# Rtx_Power_Filter.net
KiCad netlist of a schematic drawn in EAGLE
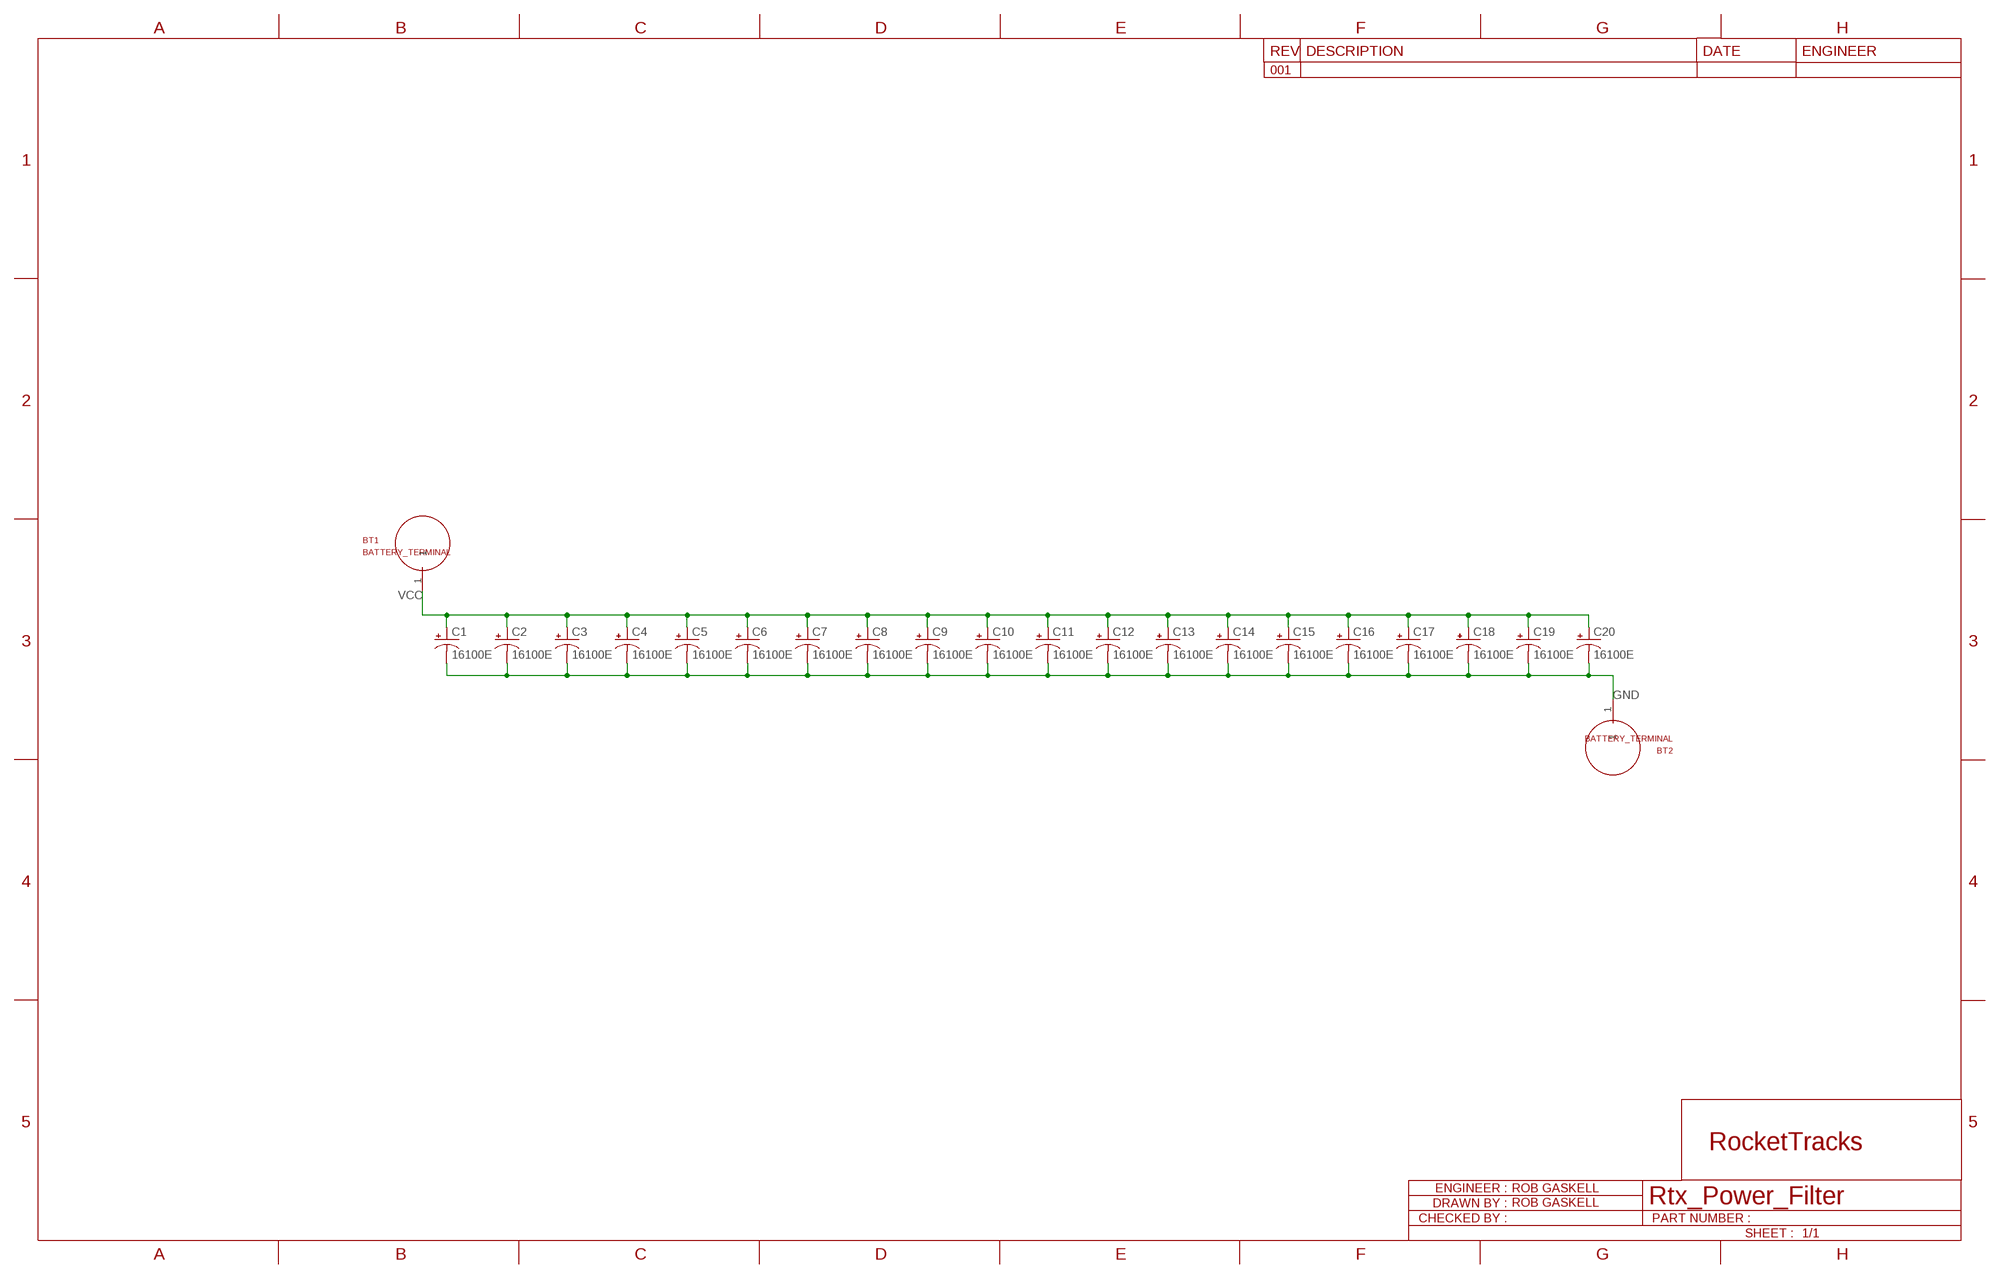
[diagram p0: schematic, sheet 1]

(export (version "E")
  (design (tool "Eeschema 10.0.6"))
  (components
    (comp (ref "BT1")
      (value "BATTERY_TERMINAL")
      (footprint "eagle-import:BATTERY_TERMINAL")
      (libsource (lib "eagle-import") (part "BATTERY_TERMINAL"))
    )
    (comp (ref "BT2")
      (value "BATTERY_TERMINAL")
      (footprint "eagle-import:BATTERY_TERMINAL")
      (libsource (lib "eagle-import") (part "BATTERY_TERMINAL"))
    )
    (comp (ref "C1")
      (value "16100E")
      (footprint "eagle-import:16100")
      (libsource (lib "eagle-import") (part "16100E"))
    )
    (comp (ref "C2")
      (value "16100E")
      (footprint "eagle-import:16100")
      (libsource (lib "eagle-import") (part "16100E"))
    )
    (comp (ref "C3")
      (value "16100E")
      (footprint "eagle-import:16100")
      (libsource (lib "eagle-import") (part "16100E"))
    )
    (comp (ref "C4")
      (value "16100E")
      (footprint "eagle-import:16100")
      (libsource (lib "eagle-import") (part "16100E"))
    )
    (comp (ref "C5")
      (value "16100E")
      (footprint "eagle-import:16100")
      (libsource (lib "eagle-import") (part "16100E"))
    )
    (comp (ref "C6")
      (value "16100E")
      (footprint "eagle-import:16100")
      (libsource (lib "eagle-import") (part "16100E"))
    )
    (comp (ref "C7")
      (value "16100E")
      (footprint "eagle-import:16100")
      (libsource (lib "eagle-import") (part "16100E"))
    )
    (comp (ref "C8")
      (value "16100E")
      (footprint "eagle-import:16100")
      (libsource (lib "eagle-import") (part "16100E"))
    )
    (comp (ref "C9")
      (value "16100E")
      (footprint "eagle-import:16100")
      (libsource (lib "eagle-import") (part "16100E"))
    )
    (comp (ref "C10")
      (value "16100E")
      (footprint "eagle-import:16100")
      (libsource (lib "eagle-import") (part "16100E"))
    )
    (comp (ref "C11")
      (value "16100E")
      (footprint "eagle-import:16100")
      (libsource (lib "eagle-import") (part "16100E"))
    )
    (comp (ref "C12")
      (value "16100E")
      (footprint "eagle-import:16100")
      (libsource (lib "eagle-import") (part "16100E"))
    )
    (comp (ref "C13")
      (value "16100E")
      (footprint "eagle-import:16100")
      (libsource (lib "eagle-import") (part "16100E"))
    )
    (comp (ref "C14")
      (value "16100E")
      (footprint "eagle-import:16100")
      (libsource (lib "eagle-import") (part "16100E"))
    )
    (comp (ref "C15")
      (value "16100E")
      (footprint "eagle-import:16100")
      (libsource (lib "eagle-import") (part "16100E"))
    )
    (comp (ref "C16")
      (value "16100E")
      (footprint "eagle-import:16100")
      (libsource (lib "eagle-import") (part "16100E"))
    )
    (comp (ref "C17")
      (value "16100E")
      (footprint "eagle-import:16100")
      (libsource (lib "eagle-import") (part "16100E"))
    )
    (comp (ref "C18")
      (value "16100E")
      (footprint "eagle-import:16100")
      (libsource (lib "eagle-import") (part "16100E"))
    )
    (comp (ref "C19")
      (value "16100E")
      (footprint "eagle-import:16100")
      (libsource (lib "eagle-import") (part "16100E"))
    )
    (comp (ref "C20")
      (value "16100E")
      (footprint "eagle-import:16100")
      (libsource (lib "eagle-import") (part "16100E"))
    )
  )
  (nets
    (net (code "1") (name "/GND") (class "Default")
      (node (ref "BT2") (pin "1") (pinfunction "1_1") (pintype "bidirectional"))
      (node (ref "C1") (pin "-") (pinfunction "-_-") (pintype "passive"))
      (node (ref "C10") (pin "-") (pinfunction "-_-") (pintype "passive"))
      (node (ref "C11") (pin "-") (pinfunction "-_-") (pintype "passive"))
      (node (ref "C12") (pin "-") (pinfunction "-_-") (pintype "passive"))
      (node (ref "C13") (pin "-") (pinfunction "-_-") (pintype "passive"))
      (node (ref "C14") (pin "-") (pinfunction "-_-") (pintype "passive"))
      (node (ref "C15") (pin "-") (pinfunction "-_-") (pintype "passive"))
      (node (ref "C16") (pin "-") (pinfunction "-_-") (pintype "passive"))
      (node (ref "C17") (pin "-") (pinfunction "-_-") (pintype "passive"))
      (node (ref "C18") (pin "-") (pinfunction "-_-") (pintype "passive"))
      (node (ref "C19") (pin "-") (pinfunction "-_-") (pintype "passive"))
      (node (ref "C2") (pin "-") (pinfunction "-_-") (pintype "passive"))
      (node (ref "C20") (pin "-") (pinfunction "-_-") (pintype "passive"))
      (node (ref "C3") (pin "-") (pinfunction "-_-") (pintype "passive"))
      (node (ref "C4") (pin "-") (pinfunction "-_-") (pintype "passive"))
      (node (ref "C5") (pin "-") (pinfunction "-_-") (pintype "passive"))
      (node (ref "C6") (pin "-") (pinfunction "-_-") (pintype "passive"))
      (node (ref "C7") (pin "-") (pinfunction "-_-") (pintype "passive"))
      (node (ref "C8") (pin "-") (pinfunction "-_-") (pintype "passive"))
      (node (ref "C9") (pin "-") (pinfunction "-_-") (pintype "passive"))
    )
    (net (code "2") (name "/VCC") (class "Default")
      (node (ref "BT1") (pin "1") (pinfunction "1_1") (pintype "bidirectional"))
      (node (ref "C1") (pin "+") (pinfunction "+_+") (pintype "passive"))
      (node (ref "C10") (pin "+") (pinfunction "+_+") (pintype "passive"))
      (node (ref "C11") (pin "+") (pinfunction "+_+") (pintype "passive"))
      (node (ref "C12") (pin "+") (pinfunction "+_+") (pintype "passive"))
      (node (ref "C13") (pin "+") (pinfunction "+_+") (pintype "passive"))
      (node (ref "C14") (pin "+") (pinfunction "+_+") (pintype "passive"))
      (node (ref "C15") (pin "+") (pinfunction "+_+") (pintype "passive"))
      (node (ref "C16") (pin "+") (pinfunction "+_+") (pintype "passive"))
      (node (ref "C17") (pin "+") (pinfunction "+_+") (pintype "passive"))
      (node (ref "C18") (pin "+") (pinfunction "+_+") (pintype "passive"))
      (node (ref "C19") (pin "+") (pinfunction "+_+") (pintype "passive"))
      (node (ref "C2") (pin "+") (pinfunction "+_+") (pintype "passive"))
      (node (ref "C20") (pin "+") (pinfunction "+_+") (pintype "passive"))
      (node (ref "C3") (pin "+") (pinfunction "+_+") (pintype "passive"))
      (node (ref "C4") (pin "+") (pinfunction "+_+") (pintype "passive"))
      (node (ref "C5") (pin "+") (pinfunction "+_+") (pintype "passive"))
      (node (ref "C6") (pin "+") (pinfunction "+_+") (pintype "passive"))
      (node (ref "C7") (pin "+") (pinfunction "+_+") (pintype "passive"))
      (node (ref "C8") (pin "+") (pinfunction "+_+") (pintype "passive"))
      (node (ref "C9") (pin "+") (pinfunction "+_+") (pintype "passive"))
    )
  )
)
